# driver_V1_6.net
KiCad netlist of a schematic drawn in Altium Designer
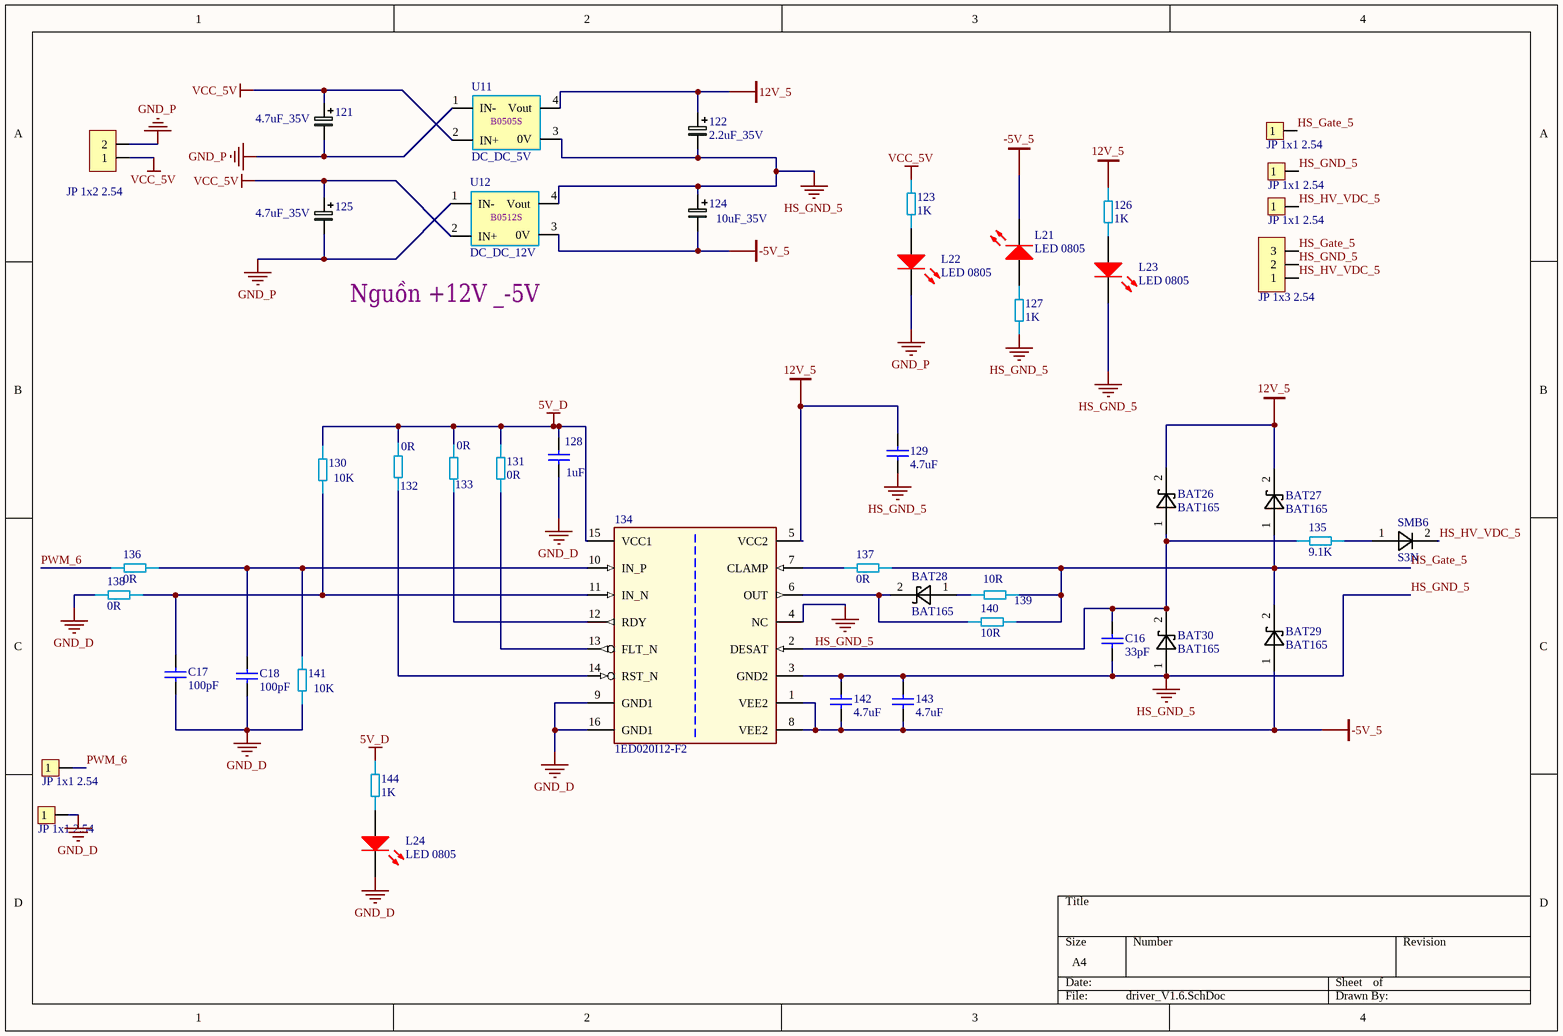
[diagram p0: driver_V1.6.SchDoc]

(export (version "E")
  (design (tool "Eeschema 10.0.6"))
  (components
    (comp (ref "121")
      (value "4.7uF_35V")
      (footprint "tu_4x5.4mm")
      (description "capacitor_electric")
      (libsource (lib "labari_altium1") (part "capacitor_electric"))
    )
    (comp (ref "122")
      (value "2.2uF_35V")
      (footprint "tu_4x5.4mm")
      (description "capacitor_electric")
      (libsource (lib "labari_altium1") (part "capacitor_electric"))
    )
    (comp (ref "123")
      (value "1K")
      (footprint "RES1206")
      (libsource (lib "labari_altium1") (part "311-0.0GRTR-ND"))
    )
    (comp (ref "124")
      (value "10uF_35V")
      (footprint "tu_4x5.4mm")
      (description "capacitor_electric")
      (libsource (lib "labari_altium1") (part "capacitor_electric"))
    )
    (comp (ref "125")
      (value "4.7uF_35V")
      (footprint "tu_4x5.4mm")
      (description "capacitor_electric")
      (libsource (lib "labari_altium1") (part "capacitor_electric"))
    )
    (comp (ref "126")
      (value "1K")
      (footprint "RES1206")
      (libsource (lib "labari_altium1") (part "311-0.0GRTR-ND"))
    )
    (comp (ref "127")
      (value "1K")
      (footprint "RES1206")
      (libsource (lib "labari_altium1") (part "311-0.0GRTR-ND"))
    )
    (comp (ref "128")
      (value "1uF")
      (footprint "Tu 0805_N")
      (libsource (lib "labari_altium1") (part "cap_0805"))
    )
    (comp (ref "129")
      (value "4.7uF")
      (footprint "tu 1206_N")
      (libsource (lib "labari_altium1") (part "cap_1210"))
    )
    (comp (ref "130")
      (value "10K")
      (footprint "RES1206")
      (libsource (lib "labari_altium1") (part "311-0.0GRTR-ND"))
    )
    (comp (ref "131")
      (value "0R")
      (footprint "RES1206")
      (libsource (lib "labari_altium1") (part "311-0.0GRTR-ND"))
    )
    (comp (ref "132")
      (value "0R")
      (footprint "RES1206")
      (libsource (lib "labari_altium1") (part "311-0.0GRTR-ND"))
    )
    (comp (ref "133")
      (value "0R")
      (footprint "RES1206")
      (libsource (lib "labari_altium1") (part "311-0.0GRTR-ND"))
    )
    (comp (ref "134")
      (value "1ED020I12-F2")
      (footprint "SOIC127P1028X264-16N-1")
      (description "Single IGBT Driver IC")
      (fields (field (name "MANUFACTURER") "Infineon Technologies"))
      (libsource (lib "labari_altium1") (part "1ED020I12-F2"))
    )
    (comp (ref "135")
      (value "9.1K")
      (footprint "RES_2512")
      (libsource (lib "labari_altium1") (part "311-0.0GRTR-ND"))
    )
    (comp (ref "136")
      (value "0R")
      (footprint "RES1206")
      (libsource (lib "labari_altium1") (part "311-0.0GRTR-ND"))
    )
    (comp (ref "137")
      (value "0R")
      (footprint "RES_2512")
      (libsource (lib "labari_altium1") (part "311-0.0GRTR-ND"))
    )
    (comp (ref "138")
      (value "0R")
      (footprint "RES1206")
      (libsource (lib "labari_altium1") (part "311-0.0GRTR-ND"))
    )
    (comp (ref "139")
      (value "10R")
      (footprint "RES_2512")
      (libsource (lib "labari_altium1") (part "311-0.0GRTR-ND"))
    )
    (comp (ref "140")
      (value "10R")
      (footprint "RES_2512")
      (libsource (lib "labari_altium1") (part "311-0.0GRTR-ND"))
    )
    (comp (ref "141")
      (value "10K")
      (footprint "RES1206")
      (libsource (lib "labari_altium1") (part "311-0.0GRTR-ND"))
    )
    (comp (ref "142")
      (value "4.7uF")
      (footprint "tu 1206_N")
      (libsource (lib "labari_altium1") (part "cap_1210"))
    )
    (comp (ref "143")
      (value "4.7uF")
      (footprint "tu 1206_N")
      (libsource (lib "labari_altium1") (part "cap_1210"))
    )
    (comp (ref "144")
      (value "1K")
      (footprint "RES1206")
      (libsource (lib "labari_altium1") (part "311-0.0GRTR-ND"))
    )
    (comp (ref "BAT26") (value "BAT165") (footprint "SMB") (libsource (lib "labari_altium1") (part "BAT165")))
    (comp (ref "BAT27") (value "BAT165") (footprint "SMB") (libsource (lib "labari_altium1") (part "BAT165")))
    (comp (ref "BAT28") (value "BAT165") (footprint "SMB") (libsource (lib "labari_altium1") (part "BAT165")))
    (comp (ref "BAT29") (value "BAT165") (footprint "SMB") (libsource (lib "labari_altium1") (part "BAT165")))
    (comp (ref "BAT30") (value "BAT165") (footprint "SMB") (libsource (lib "labari_altium1") (part "BAT165")))
    (comp (ref "C16")
      (value "33pF")
      (footprint "Tu 0805_N")
      (libsource (lib "labari_altium1") (part "cap_0805"))
    )
    (comp (ref "C17")
      (value "100pF")
      (footprint "Tu 0805_N")
      (libsource (lib "labari_altium1") (part "cap_0805"))
    )
    (comp (ref "C18")
      (value "100pF")
      (footprint "Tu 0805_N")
      (libsource (lib "labari_altium1") (part "cap_0805"))
    )
    (comp (ref "JP37")
      (value "JP 1x1 2.54")
      (footprint "test_point")
      (description "Cắm")
      (libsource (lib "labari_altium1") (part "JP 1x1 2.54 Duc Thang"))
    )
    (comp (ref "JP38")
      (value "JP 1x2 2.54")
      (footprint "JP 1x2 DT_n")
      (description "Cắm")
      (libsource (lib "labari_altium1") (part "JP 1x2 2.54 Duc Thang"))
    )
    (comp (ref "JP39")
      (value "JP 1x1 2.54")
      (footprint "test_point")
      (description "Cắm")
      (libsource (lib "labari_altium1") (part "JP 1x1 2.54 Duc Thang"))
    )
    (comp (ref "JP40")
      (value "JP 1x1 2.54")
      (footprint "test_point")
      (description "Cắm")
      (libsource (lib "labari_altium1") (part "JP 1x1 2.54 Duc Thang"))
    )
    (comp (ref "JP41")
      (value "JP 1x3 2.54")
      (footprint "XH2.54M-3")
      (description "Cắm")
      (libsource (lib "labari_altium1") (part "JP 1x3 2.54 Duc Cong"))
    )
    (comp (ref "JP42")
      (value "JP 1x1 2.54")
      (footprint "test_point")
      (description "Cắm")
      (libsource (lib "labari_altium1") (part "JP 1x1 2.54 Duc Thang"))
    )
    (comp (ref "JP43")
      (value "JP 1x1 2.54")
      (footprint "test_point")
      (description "Cắm")
      (libsource (lib "labari_altium1") (part "JP 1x1 2.54 Duc Thang"))
    )
    (comp (ref "L21")
      (value "LED 0805")
      (footprint "LED-0805-Red")
      (description "Dán")
      (libsource (lib "labari_altium1") (part "LED 0805 Do"))
    )
    (comp (ref "L22")
      (value "LED 0805")
      (footprint "LED-0805-Red")
      (description "Dán")
      (libsource (lib "labari_altium1") (part "LED 0805 Do"))
    )
    (comp (ref "L23")
      (value "LED 0805")
      (footprint "LED-0805-Red")
      (description "Dán")
      (libsource (lib "labari_altium1") (part "LED 0805 Do"))
    )
    (comp (ref "L24")
      (value "LED 0805")
      (footprint "LED-0805-Red")
      (description "Dán")
      (libsource (lib "labari_altium1") (part "LED 0805 Do"))
    )
    (comp (ref "SMB6") (value "S3N") (footprint "SMB") (libsource (lib "labari_altium1") (part "S3A-S3N")))
    (comp (ref "U11")
      (value "DC_DC_5V")
      (footprint "B0505S/D-1W")
      (libsource (lib "labari_altium1") (part "DC_DC_5v"))
    )
    (comp (ref "U12")
      (value "DC_DC_12V")
      (footprint "B0512S/D-1W")
      (libsource (lib "labari_altium1") (part "DC_DC_12v"))
    )
  )
  (nets
    (net (code "1") (name "-5V_5") (class "Default")
      (node (ref "124") (pin "2") (pinfunction "2_2") (pintype "passive"))
      (node (ref "134") (pin "1") (pinfunction "VEE2_1") (pintype "power_in"))
      (node (ref "134") (pin "8") (pinfunction "VEE2_8") (pintype "power_in"))
      (node (ref "142") (pin "1") (pinfunction "1_1") (pintype "passive"))
      (node (ref "143") (pin "1") (pinfunction "1_1") (pintype "passive"))
      (node (ref "BAT29") (pin "1") (pinfunction "1_1") (pintype "passive"))
      (node (ref "L21") (pin "2") (pinfunction "K_2") (pintype "passive"))
      (node (ref "U12") (pin "3") (pinfunction "0V_3") (pintype "passive"))
    )
    (net (code "2") (name "/HS_Gate_5") (class "Default")
      (node (ref "137") (pin "2") (pinfunction "2_2") (pintype "passive"))
      (node (ref "139") (pin "2") (pinfunction "2_2") (pintype "passive"))
      (node (ref "140") (pin "2") (pinfunction "2_2") (pintype "passive"))
      (node (ref "BAT27") (pin "1") (pinfunction "1_1") (pintype "passive"))
      (node (ref "BAT29") (pin "2") (pinfunction "2_2") (pintype "passive"))
      (node (ref "JP37") (pin "1") (pinfunction "1_1") (pintype "passive"))
      (node (ref "JP41") (pin "3") (pinfunction "3_3") (pintype "passive"))
    )
    (net (code "3") (name "/HS_HV_VDC_5") (class "Default")
      (node (ref "JP40") (pin "1") (pinfunction "1_1") (pintype "passive"))
      (node (ref "JP41") (pin "1") (pinfunction "1_1") (pintype "passive"))
      (node (ref "SMB6") (pin "2") (pinfunction "2_2") (pintype "passive"))
    )
    (net (code "4") (name "/PWM_6") (class "Default")
      (node (ref "136") (pin "2") (pinfunction "2_2") (pintype "passive"))
      (node (ref "JP42") (pin "1") (pinfunction "1_1") (pintype "passive"))
    )
    (net (code "5") (name "5V_D") (class "Default")
      (node (ref "128") (pin "2") (pinfunction "2_2") (pintype "passive"))
      (node (ref "130") (pin "2") (pinfunction "2_2") (pintype "passive"))
      (node (ref "131") (pin "1") (pinfunction "1_1") (pintype "passive"))
      (node (ref "132") (pin "2") (pinfunction "2_2") (pintype "passive"))
      (node (ref "133") (pin "1") (pinfunction "1_1") (pintype "passive"))
      (node (ref "134") (pin "15") (pinfunction "VCC1_15") (pintype "power_in"))
      (node (ref "144") (pin "1") (pinfunction "1_1") (pintype "passive"))
    )
    (net (code "6") (name "12V_5") (class "Default")
      (node (ref "122") (pin "1") (pinfunction "1_1") (pintype "passive"))
      (node (ref "126") (pin "1") (pinfunction "1_1") (pintype "passive"))
      (node (ref "129") (pin "2") (pinfunction "2_2") (pintype "passive"))
      (node (ref "134") (pin "5") (pinfunction "VCC2_5") (pintype "power_in"))
      (node (ref "BAT26") (pin "2") (pinfunction "2_2") (pintype "passive"))
      (node (ref "BAT27") (pin "2") (pinfunction "2_2") (pintype "passive"))
      (node (ref "U11") (pin "4") (pinfunction "Vout_4") (pintype "passive"))
    )
    (net (code "7") (name "GND_D") (class "Default")
      (node (ref "128") (pin "1") (pinfunction "1_1") (pintype "passive"))
      (node (ref "134") (pin "16") (pinfunction "GND1_16") (pintype "power_in"))
      (node (ref "134") (pin "9") (pinfunction "GND1_9") (pintype "power_in"))
      (node (ref "138") (pin "2") (pinfunction "2_2") (pintype "passive"))
      (node (ref "141") (pin "1") (pinfunction "1_1") (pintype "passive"))
      (node (ref "C17") (pin "1") (pinfunction "1_1") (pintype "passive"))
      (node (ref "C18") (pin "1") (pinfunction "1_1") (pintype "passive"))
      (node (ref "JP43") (pin "1") (pinfunction "1_1") (pintype "passive"))
      (node (ref "L24") (pin "2") (pinfunction "K_2") (pintype "passive"))
    )
    (net (code "8") (name "GND_P") (class "Default")
      (node (ref "121") (pin "2") (pinfunction "2_2") (pintype "passive"))
      (node (ref "125") (pin "2") (pinfunction "2_2") (pintype "passive"))
      (node (ref "JP38") (pin "2") (pinfunction "2_2") (pintype "passive"))
      (node (ref "L22") (pin "2") (pinfunction "K_2") (pintype "passive"))
      (node (ref "U11") (pin "1") (pinfunction "IN-_1") (pintype "passive"))
      (node (ref "U12") (pin "1") (pinfunction "IN-_1") (pintype "passive"))
    )
    (net (code "9") (name "HS_GND_5") (class "Default")
      (node (ref "122") (pin "2") (pinfunction "2_2") (pintype "passive"))
      (node (ref "124") (pin "1") (pinfunction "1_1") (pintype "passive"))
      (node (ref "127") (pin "2") (pinfunction "2_2") (pintype "passive"))
      (node (ref "129") (pin "1") (pinfunction "1_1") (pintype "passive"))
      (node (ref "134") (pin "3") (pinfunction "GND2_3") (pintype "power_in"))
      (node (ref "134") (pin "4") (pinfunction "NC_4") (pintype "passive"))
      (node (ref "142") (pin "2") (pinfunction "2_2") (pintype "passive"))
      (node (ref "143") (pin "2") (pinfunction "2_2") (pintype "passive"))
      (node (ref "BAT30") (pin "1") (pinfunction "1_1") (pintype "passive"))
      (node (ref "C16") (pin "1") (pinfunction "1_1") (pintype "passive"))
      (node (ref "JP39") (pin "1") (pinfunction "1_1") (pintype "passive"))
      (node (ref "JP41") (pin "2") (pinfunction "2_2") (pintype "passive"))
      (node (ref "L23") (pin "2") (pinfunction "K_2") (pintype "passive"))
      (node (ref "U11") (pin "3") (pinfunction "0V_3") (pintype "passive"))
      (node (ref "U12") (pin "4") (pinfunction "Vout_4") (pintype "passive"))
    )
    (net (code "10") (name "Net-(134-CLAMP)") (class "Default")
      (node (ref "134") (pin "7") (pinfunction "CLAMP_7") (pintype "input"))
      (node (ref "137") (pin "1") (pinfunction "1_1") (pintype "passive"))
    )
    (net (code "11") (name "Net-(134-DESAT)") (class "Default")
      (node (ref "134") (pin "2") (pinfunction "DESAT_2") (pintype "input"))
      (node (ref "135") (pin "1") (pinfunction "1_1") (pintype "passive"))
      (node (ref "BAT26") (pin "1") (pinfunction "1_1") (pintype "passive"))
      (node (ref "BAT30") (pin "2") (pinfunction "2_2") (pintype "passive"))
      (node (ref "C16") (pin "2") (pinfunction "2_2") (pintype "passive"))
    )
    (net (code "12") (name "Net-(134-FLT_N)") (class "Default")
      (node (ref "131") (pin "2") (pinfunction "2_2") (pintype "passive"))
      (node (ref "134") (pin "13") (pinfunction "FLT_N_13") (pintype "output"))
    )
    (net (code "13") (name "Net-(134-IN_N)") (class "Default")
      (node (ref "130") (pin "1") (pinfunction "1_1") (pintype "passive"))
      (node (ref "134") (pin "11") (pinfunction "IN_N_11") (pintype "input"))
      (node (ref "138") (pin "1") (pinfunction "1_1") (pintype "passive"))
      (node (ref "C17") (pin "2") (pinfunction "2_2") (pintype "passive"))
    )
    (net (code "14") (name "Net-(134-IN_P)") (class "Default")
      (node (ref "134") (pin "10") (pinfunction "IN_P_10") (pintype "input"))
      (node (ref "136") (pin "1") (pinfunction "1_1") (pintype "passive"))
      (node (ref "141") (pin "2") (pinfunction "2_2") (pintype "passive"))
      (node (ref "C18") (pin "2") (pinfunction "2_2") (pintype "passive"))
    )
    (net (code "15") (name "Net-(134-OUT)") (class "Default")
      (node (ref "134") (pin "6") (pinfunction "OUT_6") (pintype "output"))
      (node (ref "140") (pin "1") (pinfunction "1_1") (pintype "passive"))
      (node (ref "BAT28") (pin "2") (pinfunction "2_2") (pintype "passive"))
    )
    (net (code "16") (name "Net-(134-RDY)") (class "Default")
      (node (ref "133") (pin "2") (pinfunction "2_2") (pintype "passive"))
      (node (ref "134") (pin "12") (pinfunction "RDY_12") (pintype "output"))
    )
    (net (code "17") (name "Net-(134-RST_N)") (class "Default")
      (node (ref "132") (pin "1") (pinfunction "1_1") (pintype "passive"))
      (node (ref "134") (pin "14") (pinfunction "RST_N_14") (pintype "input"))
    )
    (net (code "18") (name "Net-(135-Pad2)") (class "Default")
      (node (ref "135") (pin "2") (pinfunction "2_2") (pintype "passive"))
      (node (ref "SMB6") (pin "1") (pinfunction "1_1") (pintype "passive"))
    )
    (net (code "19") (name "Net-(139-Pad1)") (class "Default")
      (node (ref "139") (pin "1") (pinfunction "1_1") (pintype "passive"))
      (node (ref "BAT28") (pin "1") (pinfunction "1_1") (pintype "passive"))
    )
    (net (code "20") (name "Net-(L21-A)") (class "Default")
      (node (ref "127") (pin "1") (pinfunction "1_1") (pintype "passive"))
      (node (ref "L21") (pin "1") (pinfunction "A_1") (pintype "passive"))
    )
    (net (code "21") (name "Net-(L22-A)") (class "Default")
      (node (ref "123") (pin "2") (pinfunction "2_2") (pintype "passive"))
      (node (ref "L22") (pin "1") (pinfunction "A_1") (pintype "passive"))
    )
    (net (code "22") (name "Net-(L23-A)") (class "Default")
      (node (ref "126") (pin "2") (pinfunction "2_2") (pintype "passive"))
      (node (ref "L23") (pin "1") (pinfunction "A_1") (pintype "passive"))
    )
    (net (code "23") (name "Net-(L24-A)") (class "Default")
      (node (ref "144") (pin "2") (pinfunction "2_2") (pintype "passive"))
      (node (ref "L24") (pin "1") (pinfunction "A_1") (pintype "passive"))
    )
    (net (code "24") (name "VCC_5V") (class "Default")
      (node (ref "121") (pin "1") (pinfunction "1_1") (pintype "passive"))
      (node (ref "123") (pin "1") (pinfunction "1_1") (pintype "passive"))
      (node (ref "125") (pin "1") (pinfunction "1_1") (pintype "passive"))
      (node (ref "JP38") (pin "1") (pinfunction "1_1") (pintype "passive"))
      (node (ref "U11") (pin "2") (pinfunction "IN+_2") (pintype "passive"))
      (node (ref "U12") (pin "2") (pinfunction "IN+_2") (pintype "passive"))
    )
  )
)
